# 3310JACKBOARD.net
KiCad netlist of a schematic drawn in EAGLE
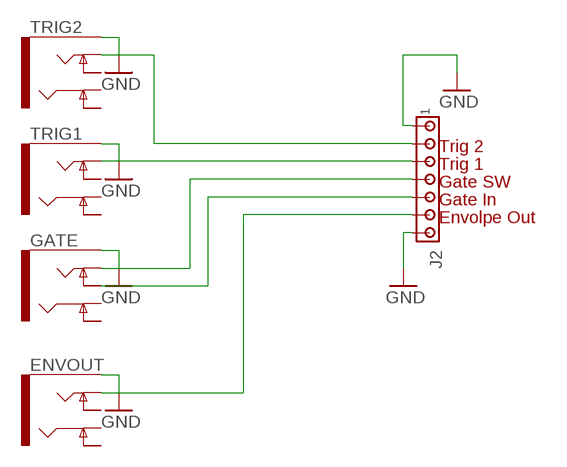
[diagram p0: schematic, sheet 1]

(export (version "E")
  (design (tool "Eeschema 10.0.6"))
  (components
    (comp (ref "ENVOUT")
      (value "AUDIO_JACK_TRS_0.25\"_PTH_VERTICAL")
      (footprint "eagle-import:AUDIO_JACK_0.25__TRS_PTH_VERTICAL")
      (libsource (lib "eagle-import") (part "AUDIO_JACK_TRS_0.25{dblquote}_PTH_VERTICAL"))
    )
    (comp (ref "GATE")
      (value "AUDIO_JACK_TRS_0.25\"_PTH_VERTICAL")
      (footprint "eagle-import:AUDIO_JACK_0.25__TRS_PTH_VERTICAL")
      (libsource (lib "eagle-import") (part "AUDIO_JACK_TRS_0.25{dblquote}_PTH_VERTICAL"))
    )
    (comp (ref "J2")
      (value "MTA07-100")
      (footprint "eagle-import:10X07MTA")
      (libsource (lib "eagle-import") (part "MTA07-100"))
    )
    (comp (ref "TRIG1")
      (value "AUDIO_JACK_TRS_0.25\"_PTH_VERTICAL")
      (footprint "eagle-import:AUDIO_JACK_0.25__TRS_PTH_VERTICAL")
      (libsource (lib "eagle-import") (part "AUDIO_JACK_TRS_0.25{dblquote}_PTH_VERTICAL"))
    )
    (comp (ref "TRIG2")
      (value "AUDIO_JACK_TRS_0.25\"_PTH_VERTICAL")
      (footprint "eagle-import:AUDIO_JACK_0.25__TRS_PTH_VERTICAL")
      (libsource (lib "eagle-import") (part "AUDIO_JACK_TRS_0.25{dblquote}_PTH_VERTICAL"))
    )
  )
  (nets
    (net (code "1") (name "GND") (class "Default")
      (node (ref "ENVOUT") (pin "SLEEVE") (pinfunction "EARTH_SLEEVE") (pintype "bidirectional"))
      (node (ref "GATE") (pin "SLEEVE") (pinfunction "EARTH_SLEEVE") (pintype "bidirectional"))
      (node (ref "J2") (pin "1") (pinfunction "1_1") (pintype "passive"))
      (node (ref "J2") (pin "7") (pinfunction "7_7") (pintype "passive"))
      (node (ref "TRIG1") (pin "SLEEVE") (pinfunction "EARTH_SLEEVE") (pintype "bidirectional"))
      (node (ref "TRIG2") (pin "SLEEVE") (pinfunction "EARTH_SLEEVE") (pintype "bidirectional"))
    )
    (net (code "2") (name "Net-(ENVOUT-PadTIP)") (class "Default")
      (node (ref "ENVOUT") (pin "TIP") (pinfunction "TIP_TIP") (pintype "bidirectional"))
      (node (ref "J2") (pin "6") (pinfunction "6_6") (pintype "passive"))
    )
    (net (code "3") (name "Net-(GATE-PadTIP)") (class "Default")
      (node (ref "GATE") (pin "TIP") (pinfunction "TIP_TIP") (pintype "bidirectional"))
      (node (ref "J2") (pin "4") (pinfunction "4_4") (pintype "passive"))
    )
    (net (code "4") (name "Net-(GATE-PadTIP-NORM)") (class "Default")
      (node (ref "GATE") (pin "TIP-NORM") (pinfunction "TIP-NORM_TIP-NORM") (pintype "bidirectional"))
      (node (ref "J2") (pin "5") (pinfunction "5_5") (pintype "passive"))
    )
    (net (code "5") (name "Net-(J2-Pad2)") (class "Default")
      (node (ref "J2") (pin "2") (pinfunction "2_2") (pintype "passive"))
      (node (ref "TRIG2") (pin "TIP") (pinfunction "TIP_TIP") (pintype "bidirectional"))
    )
    (net (code "6") (name "Net-(J2-Pad3)") (class "Default")
      (node (ref "J2") (pin "3") (pinfunction "3_3") (pintype "passive"))
      (node (ref "TRIG1") (pin "TIP") (pinfunction "TIP_TIP") (pintype "bidirectional"))
    )
    (net (code "7") (name "unconnected-(ENVOUT-PadRING)") (class "Default")
      (node (ref "ENVOUT") (pin "RING") (pinfunction "RING_RING") (pintype "bidirectional"))
    )
    (net (code "8") (name "unconnected-(ENVOUT-PadRING-NORM)") (class "Default")
      (node (ref "ENVOUT") (pin "RING-NORM") (pinfunction "RING-NORM_RING-NORM") (pintype "bidirectional"))
    )
    (net (code "9") (name "unconnected-(ENVOUT-PadTIP-NORM)") (class "Default")
      (node (ref "ENVOUT") (pin "TIP-NORM") (pinfunction "TIP-NORM_TIP-NORM") (pintype "bidirectional"))
    )
    (net (code "10") (name "unconnected-(GATE-PadRING)") (class "Default")
      (node (ref "GATE") (pin "RING") (pinfunction "RING_RING") (pintype "bidirectional"))
    )
    (net (code "11") (name "unconnected-(GATE-PadRING-NORM)") (class "Default")
      (node (ref "GATE") (pin "RING-NORM") (pinfunction "RING-NORM_RING-NORM") (pintype "bidirectional"))
    )
    (net (code "12") (name "unconnected-(TRIG1-PadRING)") (class "Default")
      (node (ref "TRIG1") (pin "RING") (pinfunction "RING_RING") (pintype "bidirectional"))
    )
    (net (code "13") (name "unconnected-(TRIG1-PadRING-NORM)") (class "Default")
      (node (ref "TRIG1") (pin "RING-NORM") (pinfunction "RING-NORM_RING-NORM") (pintype "bidirectional"))
    )
    (net (code "14") (name "unconnected-(TRIG1-PadTIP-NORM)") (class "Default")
      (node (ref "TRIG1") (pin "TIP-NORM") (pinfunction "TIP-NORM_TIP-NORM") (pintype "bidirectional"))
    )
    (net (code "15") (name "unconnected-(TRIG2-PadRING)") (class "Default")
      (node (ref "TRIG2") (pin "RING") (pinfunction "RING_RING") (pintype "bidirectional"))
    )
    (net (code "16") (name "unconnected-(TRIG2-PadRING-NORM)") (class "Default")
      (node (ref "TRIG2") (pin "RING-NORM") (pinfunction "RING-NORM_RING-NORM") (pintype "bidirectional"))
    )
    (net (code "17") (name "unconnected-(TRIG2-PadTIP-NORM)") (class "Default")
      (node (ref "TRIG2") (pin "TIP-NORM") (pinfunction "TIP-NORM_TIP-NORM") (pintype "bidirectional"))
    )
  )
)
